# ATXmega64A4U_1.net
KiCad netlist of a schematic drawn in EAGLE
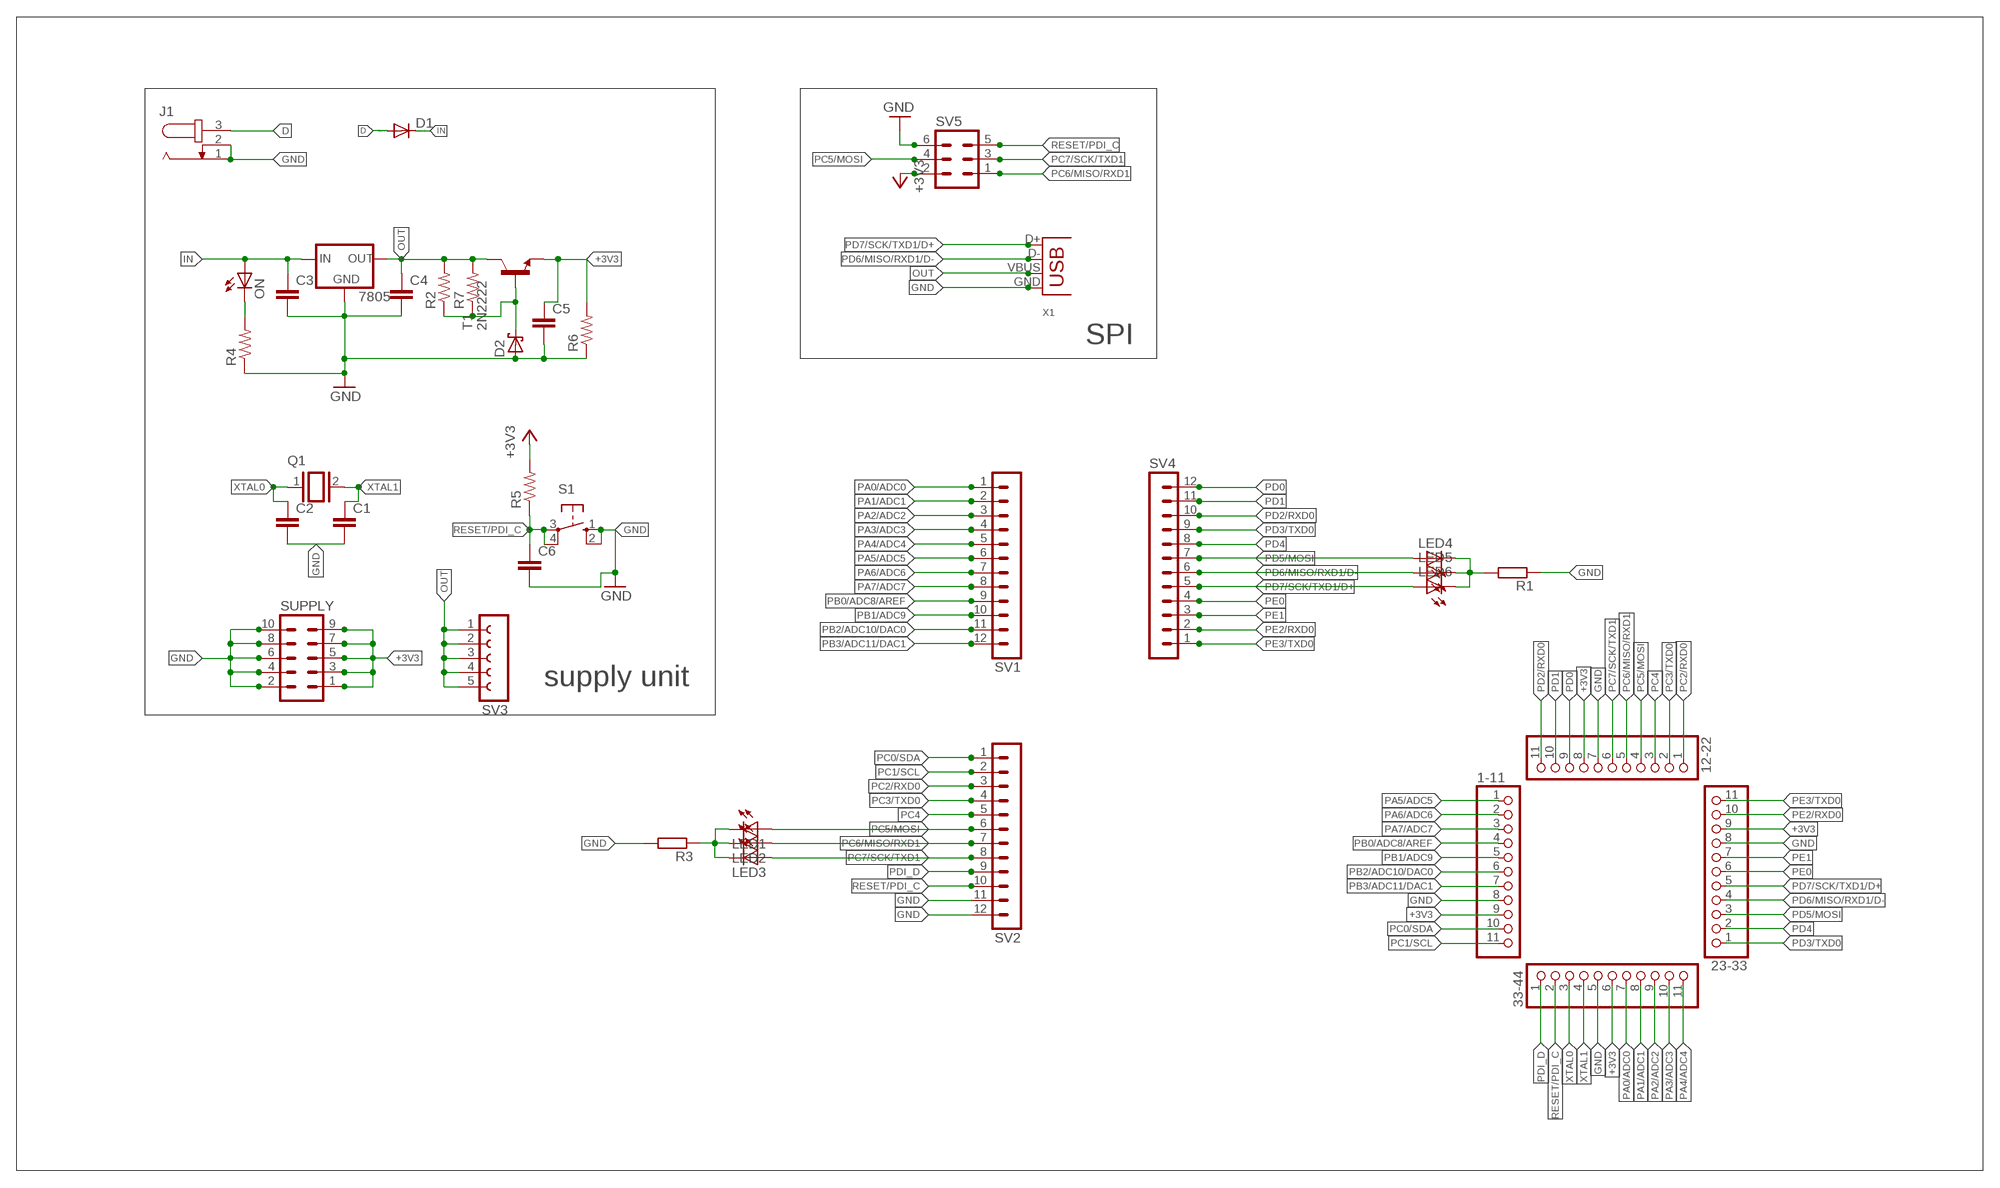
[diagram p0: schematic, sheet 1]

(export (version "E")
  (design (tool "Eeschema 10.0.6"))
  (components
    (comp (ref "1-11")
      (value "PINHD-1X11/LONG")
      (footprint "eagle-import:1X11")
      (libsource (lib "eagle-import") (part "PINHD-1X11/LONG"))
    )
    (comp (ref "12-22")
      (value "PINHD-1X11/LONG")
      (footprint "eagle-import:1X11")
      (libsource (lib "eagle-import") (part "PINHD-1X11/LONG"))
    )
    (comp (ref "23-33")
      (value "PINHD-1X11/LONG")
      (footprint "eagle-import:1X11")
      (libsource (lib "eagle-import") (part "PINHD-1X11/LONG"))
    )
    (comp (ref "33-44")
      (value "PINHD-1X11/LONG")
      (footprint "eagle-import:1X11")
      (libsource (lib "eagle-import") (part "PINHD-1X11/LONG"))
    )
    (comp (ref "7805")
      (value "78XXL")
      (footprint "eagle-import:78XXL")
      (libsource (lib "eagle-import") (part "78XXL"))
    )
    (comp (ref "C1")
      (value "C-EU025-025X050")
      (footprint "eagle-import:C025-025X050")
      (libsource (lib "eagle-import") (part "C-EU025-025X050"))
    )
    (comp (ref "C2")
      (value "C-EU025-025X050")
      (footprint "eagle-import:C025-025X050")
      (libsource (lib "eagle-import") (part "C-EU025-025X050"))
    )
    (comp (ref "C3")
      (value "C-EU025-025X050")
      (footprint "eagle-import:C025-025X050")
      (libsource (lib "eagle-import") (part "C-EU025-025X050"))
    )
    (comp (ref "C4")
      (value "C-EU025-025X050")
      (footprint "eagle-import:C025-025X050")
      (libsource (lib "eagle-import") (part "C-EU025-025X050"))
    )
    (comp (ref "C5")
      (value "C-EU025-025X050")
      (footprint "eagle-import:C025-025X050")
      (libsource (lib "eagle-import") (part "C-EU025-025X050"))
    )
    (comp (ref "C6")
      (value "C-EU025-025X050")
      (footprint "eagle-import:C025-025X050")
      (libsource (lib "eagle-import") (part "C-EU025-025X050"))
    )
    (comp (ref "D1")
      (value "1N4004")
      (footprint "eagle-import:DO41-10")
      (libsource (lib "eagle-import") (part "1N4004"))
    )
    (comp (ref "D2")
      (value "SCHOTTKY-DIODEDO35-7")
      (footprint "eagle-import:DO35-7")
      (libsource (lib "eagle-import") (part "SCHOTTKY-DIODEDO35-7"))
    )
    (comp (ref "J1")
      (value "JACK-PLUG0")
      (footprint "eagle-import:SPC4077")
      (libsource (lib "eagle-import") (part "JACK-PLUG0"))
    )
    (comp (ref "LED1")
      (value "LEDCHIPLED_0805")
      (footprint "eagle-import:CHIPLED_0805")
      (libsource (lib "eagle-import") (part "LEDCHIPLED_0805"))
    )
    (comp (ref "LED2")
      (value "LEDCHIPLED_0805")
      (footprint "eagle-import:CHIPLED_0805")
      (libsource (lib "eagle-import") (part "LEDCHIPLED_0805"))
    )
    (comp (ref "LED3")
      (value "LEDCHIPLED_0805")
      (footprint "eagle-import:CHIPLED_0805")
      (libsource (lib "eagle-import") (part "LEDCHIPLED_0805"))
    )
    (comp (ref "LED4")
      (value "LEDCHIPLED_0805")
      (footprint "eagle-import:CHIPLED_0805")
      (libsource (lib "eagle-import") (part "LEDCHIPLED_0805"))
    )
    (comp (ref "LED5")
      (value "LEDCHIPLED_0805")
      (footprint "eagle-import:CHIPLED_0805")
      (libsource (lib "eagle-import") (part "LEDCHIPLED_0805"))
    )
    (comp (ref "LED6")
      (value "LEDCHIPLED_0805")
      (footprint "eagle-import:CHIPLED_0805")
      (libsource (lib "eagle-import") (part "LEDCHIPLED_0805"))
    )
    (comp (ref "ON")
      (value "LEDCHIP-LED0805")
      (footprint "eagle-import:CHIP-LED0805")
      (libsource (lib "eagle-import") (part "LEDCHIP-LED0805"))
    )
    (comp (ref "Q1")
      (value "XTAL/S")
      (footprint "eagle-import:QS")
      (libsource (lib "eagle-import") (part "XTAL/S"))
    )
    (comp (ref "R1")
      (value "R-EU_0207/7")
      (footprint "eagle-import:0207_7")
      (libsource (lib "eagle-import") (part "R-EU_0207/7"))
    )
    (comp (ref "R2")
      (value "R-US_0207/7")
      (footprint "eagle-import:0207_7")
      (libsource (lib "eagle-import") (part "R-US_0207/7"))
    )
    (comp (ref "R3")
      (value "R-EU_0207/7")
      (footprint "eagle-import:0207_7")
      (libsource (lib "eagle-import") (part "R-EU_0207/7"))
    )
    (comp (ref "R4")
      (value "R-US_0207/7")
      (footprint "eagle-import:0207_7")
      (libsource (lib "eagle-import") (part "R-US_0207/7"))
    )
    (comp (ref "R5")
      (value "R-US_0207/7")
      (footprint "eagle-import:0207_7")
      (libsource (lib "eagle-import") (part "R-US_0207/7"))
    )
    (comp (ref "R6")
      (value "R-US_0207/7")
      (footprint "eagle-import:0207_7")
      (libsource (lib "eagle-import") (part "R-US_0207/7"))
    )
    (comp (ref "R7")
      (value "R-US_0207/7")
      (footprint "eagle-import:0207_7")
      (libsource (lib "eagle-import") (part "R-US_0207/7"))
    )
    (comp (ref "S1")
      (value "10-XX")
      (footprint "eagle-import:B3F-10XX")
      (fields (field (name "MPN") "B3F-1000"))
      (libsource (lib "eagle-import") (part "10-XX"))
    )
    (comp (ref "SUPPLY")
      (value "MA05-2")
      (footprint "eagle-import:MA05-2")
      (libsource (lib "eagle-import") (part "MA05-2"))
    )
    (comp (ref "SV1")
      (value "MA12-1")
      (footprint "eagle-import:MA12-1")
      (libsource (lib "eagle-import") (part "MA12-1"))
    )
    (comp (ref "SV2")
      (value "MA12-1")
      (footprint "eagle-import:MA12-1")
      (libsource (lib "eagle-import") (part "MA12-1"))
    )
    (comp (ref "SV3")
      (value "FE05-1")
      (footprint "eagle-import:FE05-1")
      (libsource (lib "eagle-import") (part "FE05-1"))
    )
    (comp (ref "SV4")
      (value "MA12-1")
      (footprint "eagle-import:MA12-1")
      (libsource (lib "eagle-import") (part "MA12-1"))
    )
    (comp (ref "SV5")
      (value "MA03-2")
      (footprint "eagle-import:MA03-2")
      (libsource (lib "eagle-import") (part "MA03-2"))
    )
    (comp (ref "T1")
      (value "2N2222")
      (footprint "eagle-import:TO18")
      (libsource (lib "eagle-import") (part "2N2222"))
    )
    (comp (ref "X1")
      (value "USB-B-H")
      (footprint "eagle-import:USB-B-H")
      (libsource (lib "eagle-import") (part "USB-B-H"))
    )
  )
  (nets
    (net (code "1") (name "+3V3") (class "Default")
      (node (ref "1-11") (pin "9") (pinfunction "9_9") (pintype "passive"))
      (node (ref "12-22") (pin "8") (pinfunction "8_8") (pintype "passive"))
      (node (ref "23-33") (pin "9") (pinfunction "9_9") (pintype "passive"))
      (node (ref "33-44") (pin "6") (pinfunction "6_6") (pintype "passive"))
      (node (ref "C5") (pin "1") (pinfunction "1_1") (pintype "passive"))
      (node (ref "R5") (pin "2") (pinfunction "2_2") (pintype "passive"))
      (node (ref "R6") (pin "2") (pinfunction "2_2") (pintype "passive"))
      (node (ref "SUPPLY") (pin "1") (pinfunction "1_1") (pintype "passive"))
      (node (ref "SUPPLY") (pin "3") (pinfunction "3_3") (pintype "passive"))
      (node (ref "SUPPLY") (pin "5") (pinfunction "5_5") (pintype "passive"))
      (node (ref "SUPPLY") (pin "7") (pinfunction "7_7") (pintype "passive"))
      (node (ref "SUPPLY") (pin "9") (pinfunction "9_9") (pintype "passive"))
      (node (ref "SV5") (pin "2") (pinfunction "2_2") (pintype "passive"))
      (node (ref "T1") (pin "1") (pinfunction "E_1") (pintype "passive"))
    )
    (net (code "2") (name "D") (class "Default")
      (node (ref "D1") (pin "A") (pinfunction "A_A") (pintype "passive"))
      (node (ref "J1") (pin "3") (pinfunction "3_3") (pintype "passive"))
    )
    (net (code "3") (name "GND") (class "Default")
      (node (ref "1-11") (pin "8") (pinfunction "8_8") (pintype "passive"))
      (node (ref "12-22") (pin "7") (pinfunction "7_7") (pintype "passive"))
      (node (ref "23-33") (pin "8") (pinfunction "8_8") (pintype "passive"))
      (node (ref "33-44") (pin "5") (pinfunction "5_5") (pintype "passive"))
      (node (ref "7805") (pin "GND") (pinfunction "GND_GND") (pintype "input"))
      (node (ref "C1") (pin "2") (pinfunction "2_2") (pintype "passive"))
      (node (ref "C2") (pin "2") (pinfunction "2_2") (pintype "passive"))
      (node (ref "C3") (pin "2") (pinfunction "2_2") (pintype "passive"))
      (node (ref "C4") (pin "2") (pinfunction "2_2") (pintype "passive"))
      (node (ref "C5") (pin "2") (pinfunction "2_2") (pintype "passive"))
      (node (ref "C6") (pin "2") (pinfunction "2_2") (pintype "passive"))
      (node (ref "D2") (pin "A") (pinfunction "A_A") (pintype "passive"))
      (node (ref "J1") (pin "1") (pinfunction "1_1") (pintype "passive"))
      (node (ref "J1") (pin "2") (pinfunction "2_2") (pintype "passive"))
      (node (ref "R1") (pin "1") (pinfunction "1_1") (pintype "passive"))
      (node (ref "R3") (pin "2") (pinfunction "2_2") (pintype "passive"))
      (node (ref "R4") (pin "1") (pinfunction "1_1") (pintype "passive"))
      (node (ref "R6") (pin "1") (pinfunction "1_1") (pintype "passive"))
      (node (ref "S1") (pin "1") (pinfunction "S_1") (pintype "passive"))
      (node (ref "S1") (pin "2") (pinfunction "S1_2") (pintype "passive"))
      (node (ref "SUPPLY") (pin "10") (pinfunction "10_10") (pintype "passive"))
      (node (ref "SUPPLY") (pin "2") (pinfunction "2_2") (pintype "passive"))
      (node (ref "SUPPLY") (pin "4") (pinfunction "4_4") (pintype "passive"))
      (node (ref "SUPPLY") (pin "6") (pinfunction "6_6") (pintype "passive"))
      (node (ref "SUPPLY") (pin "8") (pinfunction "8_8") (pintype "passive"))
      (node (ref "SV2") (pin "11") (pinfunction "11_11") (pintype "passive"))
      (node (ref "SV2") (pin "12") (pinfunction "12_12") (pintype "passive"))
      (node (ref "SV5") (pin "6") (pinfunction "6_6") (pintype "passive"))
      (node (ref "X1") (pin "GND") (pinfunction "GND_GND") (pintype "bidirectional"))
    )
    (net (code "4") (name "IN") (class "Default")
      (node (ref "7805") (pin "IN") (pinfunction "IN_IN") (pintype "input"))
      (node (ref "C3") (pin "1") (pinfunction "1_1") (pintype "passive"))
      (node (ref "D1") (pin "C") (pinfunction "C_C") (pintype "passive"))
      (node (ref "ON") (pin "A") (pinfunction "A_A") (pintype "passive"))
    )
    (net (code "5") (name "Net-(LED1-PadC)") (class "Default")
      (node (ref "LED1") (pin "C") (pinfunction "C_C") (pintype "passive"))
      (node (ref "LED2") (pin "C") (pinfunction "C_C") (pintype "passive"))
      (node (ref "LED3") (pin "C") (pinfunction "C_C") (pintype "passive"))
      (node (ref "R3") (pin "1") (pinfunction "1_1") (pintype "passive"))
    )
    (net (code "6") (name "Net-(LED4-PadC)") (class "Default")
      (node (ref "LED4") (pin "C") (pinfunction "C_C") (pintype "passive"))
      (node (ref "LED5") (pin "C") (pinfunction "C_C") (pintype "passive"))
      (node (ref "LED6") (pin "C") (pinfunction "C_C") (pintype "passive"))
      (node (ref "R1") (pin "2") (pinfunction "2_2") (pintype "passive"))
    )
    (net (code "7") (name "Net-(ON-PadC)") (class "Default")
      (node (ref "ON") (pin "C") (pinfunction "C_C") (pintype "passive"))
      (node (ref "R4") (pin "2") (pinfunction "2_2") (pintype "passive"))
    )
    (net (code "8") (name "Net-(T1-B)") (class "Default")
      (node (ref "D2") (pin "C") (pinfunction "C_C") (pintype "passive"))
      (node (ref "R2") (pin "1") (pinfunction "1_1") (pintype "passive"))
      (node (ref "R7") (pin "1") (pinfunction "1_1") (pintype "passive"))
      (node (ref "T1") (pin "2") (pinfunction "B_2") (pintype "passive"))
    )
    (net (code "9") (name "OUT") (class "Default")
      (node (ref "7805") (pin "OUT") (pinfunction "OUT_OUT") (pintype "passive"))
      (node (ref "C4") (pin "1") (pinfunction "1_1") (pintype "passive"))
      (node (ref "R2") (pin "2") (pinfunction "2_2") (pintype "passive"))
      (node (ref "R7") (pin "2") (pinfunction "2_2") (pintype "passive"))
      (node (ref "SV3") (pin "1") (pinfunction "1_1") (pintype "passive"))
      (node (ref "SV3") (pin "2") (pinfunction "2_2") (pintype "passive"))
      (node (ref "SV3") (pin "3") (pinfunction "3_3") (pintype "passive"))
      (node (ref "SV3") (pin "4") (pinfunction "4_4") (pintype "passive"))
      (node (ref "SV3") (pin "5") (pinfunction "5_5") (pintype "passive"))
      (node (ref "T1") (pin "3") (pinfunction "C_3") (pintype "passive"))
      (node (ref "X1") (pin "VBUS") (pinfunction "VBUS_VBUS") (pintype "bidirectional"))
    )
    (net (code "10") (name "PA0{slash}ADC0") (class "Default")
      (node (ref "33-44") (pin "7") (pinfunction "7_7") (pintype "passive"))
      (node (ref "SV1") (pin "1") (pinfunction "1_1") (pintype "passive"))
    )
    (net (code "11") (name "PA1{slash}ADC1") (class "Default")
      (node (ref "33-44") (pin "8") (pinfunction "8_8") (pintype "passive"))
      (node (ref "SV1") (pin "2") (pinfunction "2_2") (pintype "passive"))
    )
    (net (code "12") (name "PA2{slash}ADC2") (class "Default")
      (node (ref "33-44") (pin "9") (pinfunction "9_9") (pintype "passive"))
      (node (ref "SV1") (pin "3") (pinfunction "3_3") (pintype "passive"))
    )
    (net (code "13") (name "PA3{slash}ADC3") (class "Default")
      (node (ref "33-44") (pin "10") (pinfunction "10_10") (pintype "passive"))
      (node (ref "SV1") (pin "4") (pinfunction "4_4") (pintype "passive"))
    )
    (net (code "14") (name "PA4{slash}ADC4") (class "Default")
      (node (ref "33-44") (pin "11") (pinfunction "11_11") (pintype "passive"))
      (node (ref "SV1") (pin "5") (pinfunction "5_5") (pintype "passive"))
    )
    (net (code "15") (name "PA5{slash}ADC5") (class "Default")
      (node (ref "1-11") (pin "1") (pinfunction "1_1") (pintype "passive"))
      (node (ref "SV1") (pin "6") (pinfunction "6_6") (pintype "passive"))
    )
    (net (code "16") (name "PA6{slash}ADC6") (class "Default")
      (node (ref "1-11") (pin "2") (pinfunction "2_2") (pintype "passive"))
      (node (ref "SV1") (pin "7") (pinfunction "7_7") (pintype "passive"))
    )
    (net (code "17") (name "PA7{slash}ADC7") (class "Default")
      (node (ref "1-11") (pin "3") (pinfunction "3_3") (pintype "passive"))
      (node (ref "SV1") (pin "8") (pinfunction "8_8") (pintype "passive"))
    )
    (net (code "18") (name "PB0{slash}ADC8{slash}AREF") (class "Default")
      (node (ref "1-11") (pin "4") (pinfunction "4_4") (pintype "passive"))
      (node (ref "SV1") (pin "9") (pinfunction "9_9") (pintype "passive"))
    )
    (net (code "19") (name "PB1{slash}ADC9") (class "Default")
      (node (ref "1-11") (pin "5") (pinfunction "5_5") (pintype "passive"))
      (node (ref "SV1") (pin "10") (pinfunction "10_10") (pintype "passive"))
    )
    (net (code "20") (name "PB2{slash}ADC10{slash}DAC0") (class "Default")
      (node (ref "1-11") (pin "6") (pinfunction "6_6") (pintype "passive"))
      (node (ref "SV1") (pin "11") (pinfunction "11_11") (pintype "passive"))
    )
    (net (code "21") (name "PB3{slash}ADC11{slash}DAC1") (class "Default")
      (node (ref "1-11") (pin "7") (pinfunction "7_7") (pintype "passive"))
      (node (ref "SV1") (pin "12") (pinfunction "12_12") (pintype "passive"))
    )
    (net (code "22") (name "PC0{slash}SDA") (class "Default")
      (node (ref "1-11") (pin "10") (pinfunction "10_10") (pintype "passive"))
      (node (ref "SV2") (pin "1") (pinfunction "1_1") (pintype "passive"))
    )
    (net (code "23") (name "PC1{slash}SCL") (class "Default")
      (node (ref "1-11") (pin "11") (pinfunction "11_11") (pintype "passive"))
      (node (ref "SV2") (pin "2") (pinfunction "2_2") (pintype "passive"))
    )
    (net (code "24") (name "PC2{slash}RXD0") (class "Default")
      (node (ref "12-22") (pin "1") (pinfunction "1_1") (pintype "passive"))
      (node (ref "SV2") (pin "3") (pinfunction "3_3") (pintype "passive"))
    )
    (net (code "25") (name "PC3{slash}TXD0") (class "Default")
      (node (ref "12-22") (pin "2") (pinfunction "2_2") (pintype "passive"))
      (node (ref "SV2") (pin "4") (pinfunction "4_4") (pintype "passive"))
    )
    (net (code "26") (name "PC4") (class "Default")
      (node (ref "12-22") (pin "3") (pinfunction "3_3") (pintype "passive"))
      (node (ref "SV2") (pin "5") (pinfunction "5_5") (pintype "passive"))
    )
    (net (code "27") (name "PC5{slash}MOSI") (class "Default")
      (node (ref "12-22") (pin "4") (pinfunction "4_4") (pintype "passive"))
      (node (ref "LED1") (pin "A") (pinfunction "A_A") (pintype "passive"))
      (node (ref "SV2") (pin "6") (pinfunction "6_6") (pintype "passive"))
      (node (ref "SV5") (pin "4") (pinfunction "4_4") (pintype "passive"))
    )
    (net (code "28") (name "PC6{slash}MISO{slash}RXD1") (class "Default")
      (node (ref "12-22") (pin "5") (pinfunction "5_5") (pintype "passive"))
      (node (ref "LED2") (pin "A") (pinfunction "A_A") (pintype "passive"))
      (node (ref "SV2") (pin "7") (pinfunction "7_7") (pintype "passive"))
      (node (ref "SV5") (pin "1") (pinfunction "1_1") (pintype "passive"))
    )
    (net (code "29") (name "PC7{slash}SCK{slash}TXD1") (class "Default")
      (node (ref "12-22") (pin "6") (pinfunction "6_6") (pintype "passive"))
      (node (ref "LED3") (pin "A") (pinfunction "A_A") (pintype "passive"))
      (node (ref "SV2") (pin "8") (pinfunction "8_8") (pintype "passive"))
      (node (ref "SV5") (pin "3") (pinfunction "3_3") (pintype "passive"))
    )
    (net (code "30") (name "PD0") (class "Default")
      (node (ref "12-22") (pin "9") (pinfunction "9_9") (pintype "passive"))
      (node (ref "SV4") (pin "12") (pinfunction "12_12") (pintype "passive"))
    )
    (net (code "31") (name "PD1") (class "Default")
      (node (ref "12-22") (pin "10") (pinfunction "10_10") (pintype "passive"))
      (node (ref "SV4") (pin "11") (pinfunction "11_11") (pintype "passive"))
    )
    (net (code "32") (name "PD2{slash}RXD0") (class "Default")
      (node (ref "12-22") (pin "11") (pinfunction "11_11") (pintype "passive"))
      (node (ref "SV4") (pin "10") (pinfunction "10_10") (pintype "passive"))
    )
    (net (code "33") (name "PD3{slash}TXD0") (class "Default")
      (node (ref "23-33") (pin "1") (pinfunction "1_1") (pintype "passive"))
      (node (ref "SV4") (pin "9") (pinfunction "9_9") (pintype "passive"))
    )
    (net (code "34") (name "PD4") (class "Default")
      (node (ref "23-33") (pin "2") (pinfunction "2_2") (pintype "passive"))
      (node (ref "SV4") (pin "8") (pinfunction "8_8") (pintype "passive"))
    )
    (net (code "35") (name "PD5{slash}MOSI") (class "Default")
      (node (ref "23-33") (pin "3") (pinfunction "3_3") (pintype "passive"))
      (node (ref "LED4") (pin "A") (pinfunction "A_A") (pintype "passive"))
      (node (ref "SV4") (pin "7") (pinfunction "7_7") (pintype "passive"))
    )
    (net (code "36") (name "PD6{slash}MISO{slash}RXD1{slash}D-") (class "Default")
      (node (ref "23-33") (pin "4") (pinfunction "4_4") (pintype "passive"))
      (node (ref "LED5") (pin "A") (pinfunction "A_A") (pintype "passive"))
      (node (ref "SV4") (pin "6") (pinfunction "6_6") (pintype "passive"))
      (node (ref "X1") (pin "D-") (pinfunction "D-_D-") (pintype "bidirectional"))
    )
    (net (code "37") (name "PD7{slash}SCK{slash}TXD1{slash}D+") (class "Default")
      (node (ref "23-33") (pin "5") (pinfunction "5_5") (pintype "passive"))
      (node (ref "LED6") (pin "A") (pinfunction "A_A") (pintype "passive"))
      (node (ref "SV4") (pin "5") (pinfunction "5_5") (pintype "passive"))
      (node (ref "X1") (pin "D+") (pinfunction "D+_D+") (pintype "bidirectional"))
    )
    (net (code "38") (name "PDI_D") (class "Default")
      (node (ref "33-44") (pin "1") (pinfunction "1_1") (pintype "passive"))
      (node (ref "SV2") (pin "9") (pinfunction "9_9") (pintype "passive"))
    )
    (net (code "39") (name "PE0") (class "Default")
      (node (ref "23-33") (pin "6") (pinfunction "6_6") (pintype "passive"))
      (node (ref "SV4") (pin "4") (pinfunction "4_4") (pintype "passive"))
    )
    (net (code "40") (name "PE1") (class "Default")
      (node (ref "23-33") (pin "7") (pinfunction "7_7") (pintype "passive"))
      (node (ref "SV4") (pin "3") (pinfunction "3_3") (pintype "passive"))
    )
    (net (code "41") (name "PE2{slash}RXD0") (class "Default")
      (node (ref "23-33") (pin "10") (pinfunction "10_10") (pintype "passive"))
      (node (ref "SV4") (pin "2") (pinfunction "2_2") (pintype "passive"))
    )
    (net (code "42") (name "PE3{slash}TXD0") (class "Default")
      (node (ref "23-33") (pin "11") (pinfunction "11_11") (pintype "passive"))
      (node (ref "SV4") (pin "1") (pinfunction "1_1") (pintype "passive"))
    )
    (net (code "43") (name "RESET{slash}PDI_C") (class "Default")
      (node (ref "33-44") (pin "2") (pinfunction "2_2") (pintype "passive"))
      (node (ref "C6") (pin "1") (pinfunction "1_1") (pintype "passive"))
      (node (ref "R5") (pin "1") (pinfunction "1_1") (pintype "passive"))
      (node (ref "S1") (pin "3") (pinfunction "P_3") (pintype "passive"))
      (node (ref "S1") (pin "4") (pinfunction "P1_4") (pintype "passive"))
      (node (ref "SV2") (pin "10") (pinfunction "10_10") (pintype "passive"))
      (node (ref "SV5") (pin "5") (pinfunction "5_5") (pintype "passive"))
    )
    (net (code "44") (name "XTAL0") (class "Default")
      (node (ref "33-44") (pin "3") (pinfunction "3_3") (pintype "passive"))
      (node (ref "C2") (pin "1") (pinfunction "1_1") (pintype "passive"))
      (node (ref "Q1") (pin "1") (pinfunction "1_1") (pintype "passive"))
    )
    (net (code "45") (name "XTAL1") (class "Default")
      (node (ref "33-44") (pin "4") (pinfunction "4_4") (pintype "passive"))
      (node (ref "C1") (pin "1") (pinfunction "1_1") (pintype "passive"))
      (node (ref "Q1") (pin "2") (pinfunction "2_2") (pintype "passive"))
    )
  )
)
